# mLRS-rx-tx-E77-E28-dualband-easysolder-v.net
KiCad netlist of a schematic drawn in EAGLE
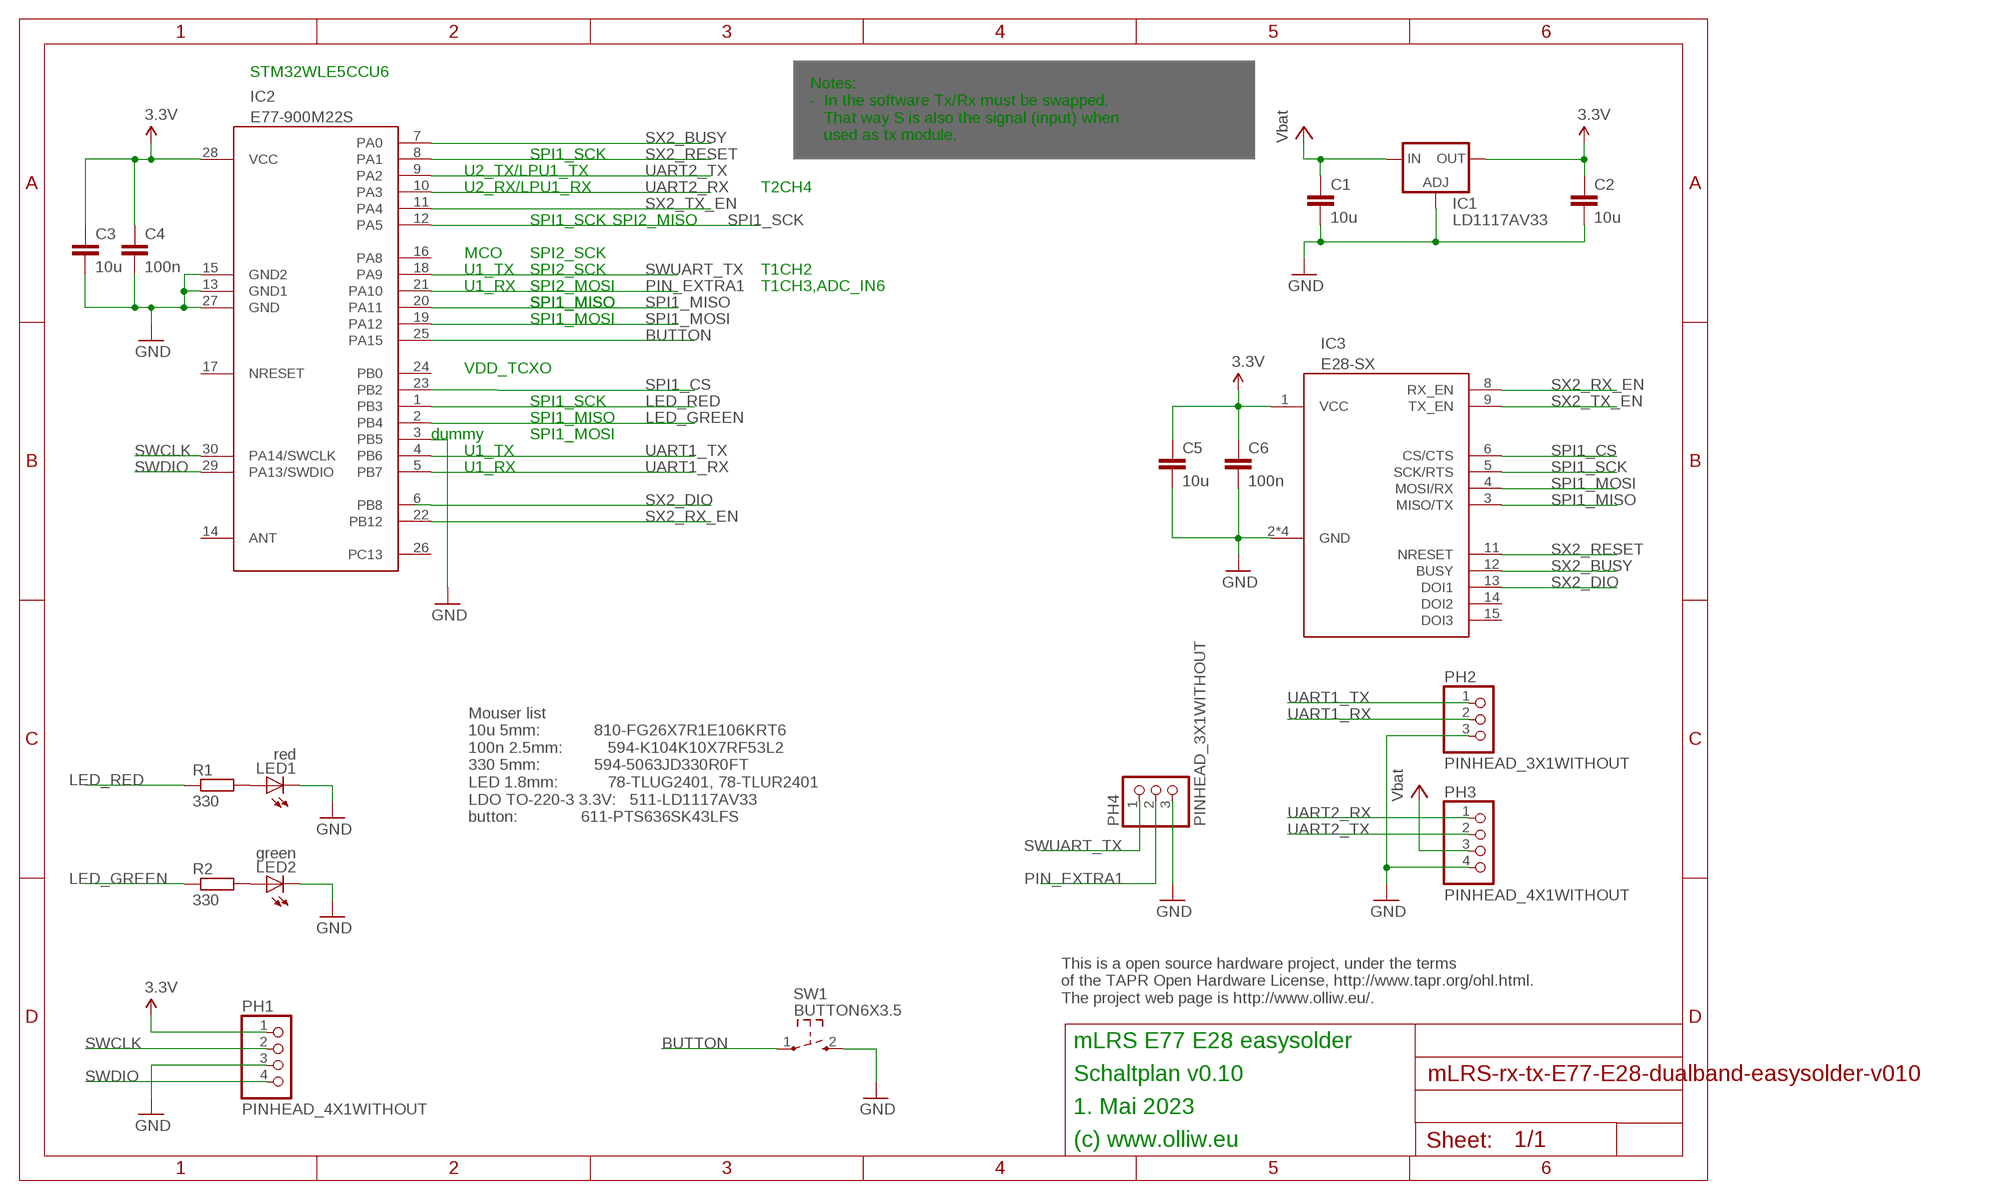
[diagram p0: schematic, sheet 1]

(export (version "E")
  (design (tool "Eeschema 10.0.6"))
  (components
    (comp (ref "C1")
      (value "10u")
      (footprint "eagle-import:C050-045X075")
      (libsource (lib "eagle-import") (part "C-EU050-045X075"))
    )
    (comp (ref "C2")
      (value "10u")
      (footprint "eagle-import:C050-045X075")
      (libsource (lib "eagle-import") (part "C-EU050-045X075"))
    )
    (comp (ref "C3")
      (value "10u")
      (footprint "eagle-import:C050-024X044")
      (libsource (lib "eagle-import") (part "C-EU050-024X044"))
    )
    (comp (ref "C4")
      (value "100n")
      (footprint "eagle-import:C025-024X044")
      (libsource (lib "eagle-import") (part "C-EU025-024X044"))
    )
    (comp (ref "C5")
      (value "10u")
      (footprint "eagle-import:C050-024X044")
      (libsource (lib "eagle-import") (part "C-EU050-024X044"))
    )
    (comp (ref "C6")
      (value "100n")
      (footprint "eagle-import:C025-024X044")
      (libsource (lib "eagle-import") (part "C-EU025-024X044"))
    )
    (comp (ref "IC1")
      (value "LD1117AV33")
      (footprint "eagle-import:TO220L1")
      (libsource (lib "eagle-import") (part "LD117A?V33"))
    )
    (comp (ref "IC2")
      (value "E77-900M22S")
      (footprint "eagle-import:E77-900M22S")
      (libsource (lib "eagle-import") (part "E77-900M22S"))
    )
    (comp (ref "IC3")
      (value "E28-SX")
      (footprint "eagle-import:E28-2G4M27SX")
      (libsource (lib "eagle-import") (part "E28-SX"))
    )
    (comp (ref "LED1")
      (value "red")
      (footprint "eagle-import:LED1.8MM")
      (libsource (lib "eagle-import") (part "LED1.8MM"))
    )
    (comp (ref "LED2")
      (value "green")
      (footprint "eagle-import:LED1.8MM")
      (libsource (lib "eagle-import") (part "LED1.8MM"))
    )
    (comp (ref "PH1")
      (value "PINHEAD_4X1WITHOUT")
      (footprint "eagle-import:PINHEAD_4X1_WO")
      (libsource (lib "eagle-import") (part "PINHEAD_4X1WITHOUT"))
    )
    (comp (ref "PH2")
      (value "PINHEAD_3X1WITHOUT")
      (footprint "eagle-import:PINHEAD_3X1_WO")
      (libsource (lib "eagle-import") (part "PINHEAD_3X1WITHOUT"))
    )
    (comp (ref "PH3")
      (value "PINHEAD_4X1WITHOUT")
      (footprint "eagle-import:PINHEAD_4X1_WO")
      (libsource (lib "eagle-import") (part "PINHEAD_4X1WITHOUT"))
    )
    (comp (ref "PH4")
      (value "PINHEAD_3X1WITHOUT")
      (footprint "eagle-import:PINHEAD_3X1_WO")
      (libsource (lib "eagle-import") (part "PINHEAD_3X1WITHOUT"))
    )
    (comp (ref "R1")
      (value "330")
      (footprint "eagle-import:R0204_6.25")
      (libsource (lib "eagle-import") (part "R_EUR0204/6.25"))
    )
    (comp (ref "R2")
      (value "330")
      (footprint "eagle-import:R0204_6.25")
      (libsource (lib "eagle-import") (part "R_EUR0204/6.25"))
    )
    (comp (ref "SW1")
      (value "BUTTON6X3.5")
      (footprint "eagle-import:BUTTON-THT")
      (libsource (lib "eagle-import") (part "BUTTON6X3.5"))
    )
  )
  (nets
    (net (code "1") (name "/BUTTON") (class "Default")
      (node (ref "IC2") (pin "25") (pinfunction "PA15_25") (pintype "bidirectional"))
      (node (ref "SW1") (pin "1") (pinfunction "1_1") (pintype "passive"))
    )
    (net (code "2") (name "/LED_GREEN") (class "Default")
      (node (ref "IC2") (pin "2") (pinfunction "PB4_2") (pintype "bidirectional"))
      (node (ref "R2") (pin "1") (pinfunction "1_1") (pintype "passive"))
    )
    (net (code "3") (name "/LED_RED") (class "Default")
      (node (ref "IC2") (pin "1") (pinfunction "PB3_1") (pintype "bidirectional"))
      (node (ref "R1") (pin "1") (pinfunction "1_1") (pintype "passive"))
    )
    (net (code "4") (name "/PIN_EXTRA1") (class "Default")
      (node (ref "IC2") (pin "21") (pinfunction "PA10_21") (pintype "bidirectional"))
      (node (ref "PH4") (pin "2") (pinfunction "3_2") (pintype "passive"))
    )
    (net (code "5") (name "/SPI1_CS") (class "Default")
      (node (ref "IC2") (pin "23") (pinfunction "PB2_23") (pintype "bidirectional"))
      (node (ref "IC3") (pin "6") (pinfunction "CS/CTS_6") (pintype "bidirectional"))
    )
    (net (code "6") (name "/SPI1_MISO") (class "Default")
      (node (ref "IC2") (pin "20") (pinfunction "PA11_20") (pintype "bidirectional"))
      (node (ref "IC3") (pin "3") (pinfunction "MISO/TX_3") (pintype "bidirectional"))
    )
    (net (code "7") (name "/SPI1_MOSI") (class "Default")
      (node (ref "IC2") (pin "19") (pinfunction "PA12_19") (pintype "bidirectional"))
      (node (ref "IC3") (pin "4") (pinfunction "MOSI/RX_4") (pintype "bidirectional"))
    )
    (net (code "8") (name "/SPI1_SCK") (class "Default")
      (node (ref "IC2") (pin "12") (pinfunction "PA5_12") (pintype "bidirectional"))
      (node (ref "IC3") (pin "5") (pinfunction "SCK/RTS_5") (pintype "bidirectional"))
    )
    (net (code "9") (name "/SWCLK") (class "Default")
      (node (ref "IC2") (pin "30") (pinfunction "PA14/SWCLK_30") (pintype "bidirectional"))
      (node (ref "PH1") (pin "2") (pinfunction "2_2") (pintype "passive"))
    )
    (net (code "10") (name "/SWDIO") (class "Default")
      (node (ref "IC2") (pin "29") (pinfunction "PA13/SWDIO_29") (pintype "bidirectional"))
      (node (ref "PH1") (pin "4") (pinfunction "4_4") (pintype "passive"))
    )
    (net (code "11") (name "/SWUART_TX") (class "Default")
      (node (ref "IC2") (pin "18") (pinfunction "PA9_18") (pintype "bidirectional"))
      (node (ref "PH4") (pin "1") (pinfunction "1_1") (pintype "passive"))
    )
    (net (code "12") (name "/SX2_BUSY") (class "Default")
      (node (ref "IC2") (pin "7") (pinfunction "PA0_7") (pintype "bidirectional"))
      (node (ref "IC3") (pin "12") (pinfunction "BUSY_12") (pintype "bidirectional"))
    )
    (net (code "13") (name "/SX2_DIO") (class "Default")
      (node (ref "IC2") (pin "6") (pinfunction "PB8_6") (pintype "bidirectional"))
      (node (ref "IC3") (pin "13") (pinfunction "DOI1_13") (pintype "bidirectional"))
    )
    (net (code "14") (name "/SX2_RESET") (class "Default")
      (node (ref "IC2") (pin "8") (pinfunction "PA1_8") (pintype "bidirectional"))
      (node (ref "IC3") (pin "11") (pinfunction "NRESET_11") (pintype "input"))
    )
    (net (code "15") (name "/SX2_RX_EN") (class "Default")
      (node (ref "IC2") (pin "22") (pinfunction "PB12_22") (pintype "bidirectional"))
      (node (ref "IC3") (pin "8") (pinfunction "RX_EN_8") (pintype "bidirectional"))
    )
    (net (code "16") (name "/SX2_TX_EN") (class "Default")
      (node (ref "IC2") (pin "11") (pinfunction "PA4_11") (pintype "bidirectional"))
      (node (ref "IC3") (pin "9") (pinfunction "TX_EN_9") (pintype "bidirectional"))
    )
    (net (code "17") (name "/UART1_RX") (class "Default")
      (node (ref "IC2") (pin "5") (pinfunction "PB7_5") (pintype "bidirectional"))
      (node (ref "PH2") (pin "2") (pinfunction "3_2") (pintype "passive"))
    )
    (net (code "18") (name "/UART1_TX") (class "Default")
      (node (ref "IC2") (pin "4") (pinfunction "PB6_4") (pintype "bidirectional"))
      (node (ref "PH2") (pin "1") (pinfunction "1_1") (pintype "passive"))
    )
    (net (code "19") (name "/UART2_RX") (class "Default")
      (node (ref "IC2") (pin "10") (pinfunction "PA3_10") (pintype "bidirectional"))
      (node (ref "PH3") (pin "1") (pinfunction "1_1") (pintype "passive"))
    )
    (net (code "20") (name "/UART2_TX") (class "Default")
      (node (ref "IC2") (pin "9") (pinfunction "PA2_9") (pintype "bidirectional"))
      (node (ref "PH3") (pin "2") (pinfunction "2_2") (pintype "passive"))
    )
    (net (code "21") (name "3.3V") (class "Default")
      (node (ref "C2") (pin "1") (pinfunction "1_1") (pintype "passive"))
      (node (ref "C3") (pin "1") (pinfunction "1_1") (pintype "passive"))
      (node (ref "C4") (pin "1") (pinfunction "1_1") (pintype "passive"))
      (node (ref "C5") (pin "1") (pinfunction "1_1") (pintype "passive"))
      (node (ref "C6") (pin "1") (pinfunction "1_1") (pintype "passive"))
      (node (ref "IC1") (pin "2") (pinfunction "OUT_2") (pintype "passive"))
      (node (ref "IC2") (pin "28") (pinfunction "VCC_28") (pintype "power_in"))
      (node (ref "IC3") (pin "1") (pinfunction "VCC_1") (pintype "power_in"))
      (node (ref "PH1") (pin "1") (pinfunction "1_1") (pintype "passive"))
    )
    (net (code "22") (name "GND") (class "Default")
      (node (ref "C1") (pin "2") (pinfunction "2_2") (pintype "passive"))
      (node (ref "C2") (pin "2") (pinfunction "2_2") (pintype "passive"))
      (node (ref "C3") (pin "2") (pinfunction "2_2") (pintype "passive"))
      (node (ref "C4") (pin "2") (pinfunction "2_2") (pintype "passive"))
      (node (ref "C5") (pin "2") (pinfunction "2_2") (pintype "passive"))
      (node (ref "C6") (pin "2") (pinfunction "2_2") (pintype "passive"))
      (node (ref "IC1") (pin "1") (pinfunction "ADJ_1") (pintype "input"))
      (node (ref "IC2") (pin "13") (pinfunction "GND1_13") (pintype "power_in"))
      (node (ref "IC2") (pin "15") (pinfunction "GND2_15") (pintype "power_in"))
      (node (ref "IC2") (pin "27") (pinfunction "GND_27") (pintype "power_in"))
      (node (ref "IC2") (pin "3") (pinfunction "PB5_3") (pintype "bidirectional"))
      (node (ref "IC3") (pin "10") (pinfunction "GND_10") (pintype "power_in"))
      (node (ref "IC3") (pin "16") (pinfunction "GND_16") (pintype "power_in"))
      (node (ref "IC3") (pin "2") (pinfunction "GND_2") (pintype "power_in"))
      (node (ref "IC3") (pin "7") (pinfunction "GND_7") (pintype "power_in"))
      (node (ref "LED1") (pin "K") (pinfunction "C_K") (pintype "passive"))
      (node (ref "LED2") (pin "K") (pinfunction "C_K") (pintype "passive"))
      (node (ref "PH1") (pin "3") (pinfunction "3_3") (pintype "passive"))
      (node (ref "PH2") (pin "3") (pinfunction "5_3") (pintype "passive"))
      (node (ref "PH3") (pin "4") (pinfunction "4_4") (pintype "passive"))
      (node (ref "PH4") (pin "3") (pinfunction "5_3") (pintype "passive"))
      (node (ref "SW1") (pin "2") (pinfunction "3_2") (pintype "passive"))
    )
    (net (code "23") (name "Net-(LED1-PadA)") (class "Default")
      (node (ref "LED1") (pin "A") (pinfunction "A_A") (pintype "passive"))
      (node (ref "R1") (pin "2") (pinfunction "2_2") (pintype "passive"))
    )
    (net (code "24") (name "Net-(LED2-PadA)") (class "Default")
      (node (ref "LED2") (pin "A") (pinfunction "A_A") (pintype "passive"))
      (node (ref "R2") (pin "2") (pinfunction "2_2") (pintype "passive"))
    )
    (net (code "25") (name "Vbat") (class "Default")
      (node (ref "C1") (pin "1") (pinfunction "1_1") (pintype "passive"))
      (node (ref "IC1") (pin "3") (pinfunction "IN_3") (pintype "input"))
      (node (ref "PH3") (pin "3") (pinfunction "3_3") (pintype "passive"))
    )
    (net (code "26") (name "unconnected-(IC2-ANT-Pad14)") (class "Default")
      (node (ref "IC2") (pin "14") (pinfunction "ANT_14") (pintype "bidirectional"))
    )
    (net (code "27") (name "unconnected-(IC2-NRESET-Pad17)") (class "Default")
      (node (ref "IC2") (pin "17") (pinfunction "NRESET_17") (pintype "input"))
    )
    (net (code "28") (name "unconnected-(IC2-PA8-Pad16)") (class "Default")
      (node (ref "IC2") (pin "16") (pinfunction "PA8_16") (pintype "bidirectional"))
    )
    (net (code "29") (name "unconnected-(IC2-PB0-Pad24)") (class "Default")
      (node (ref "IC2") (pin "24") (pinfunction "PB0_24") (pintype "bidirectional"))
    )
    (net (code "30") (name "unconnected-(IC2-PC13-Pad26)") (class "Default")
      (node (ref "IC2") (pin "26") (pinfunction "PC13_26") (pintype "bidirectional"))
    )
    (net (code "31") (name "unconnected-(IC3-DOI2-Pad14)") (class "Default")
      (node (ref "IC3") (pin "14") (pinfunction "DOI2_14") (pintype "bidirectional"))
    )
    (net (code "32") (name "unconnected-(IC3-DOI3-Pad15)") (class "Default")
      (node (ref "IC3") (pin "15") (pinfunction "DOI3_15") (pintype "bidirectional"))
    )
  )
)
